# PCB1.net
KiCad netlist of a schematic drawn in EAGLE
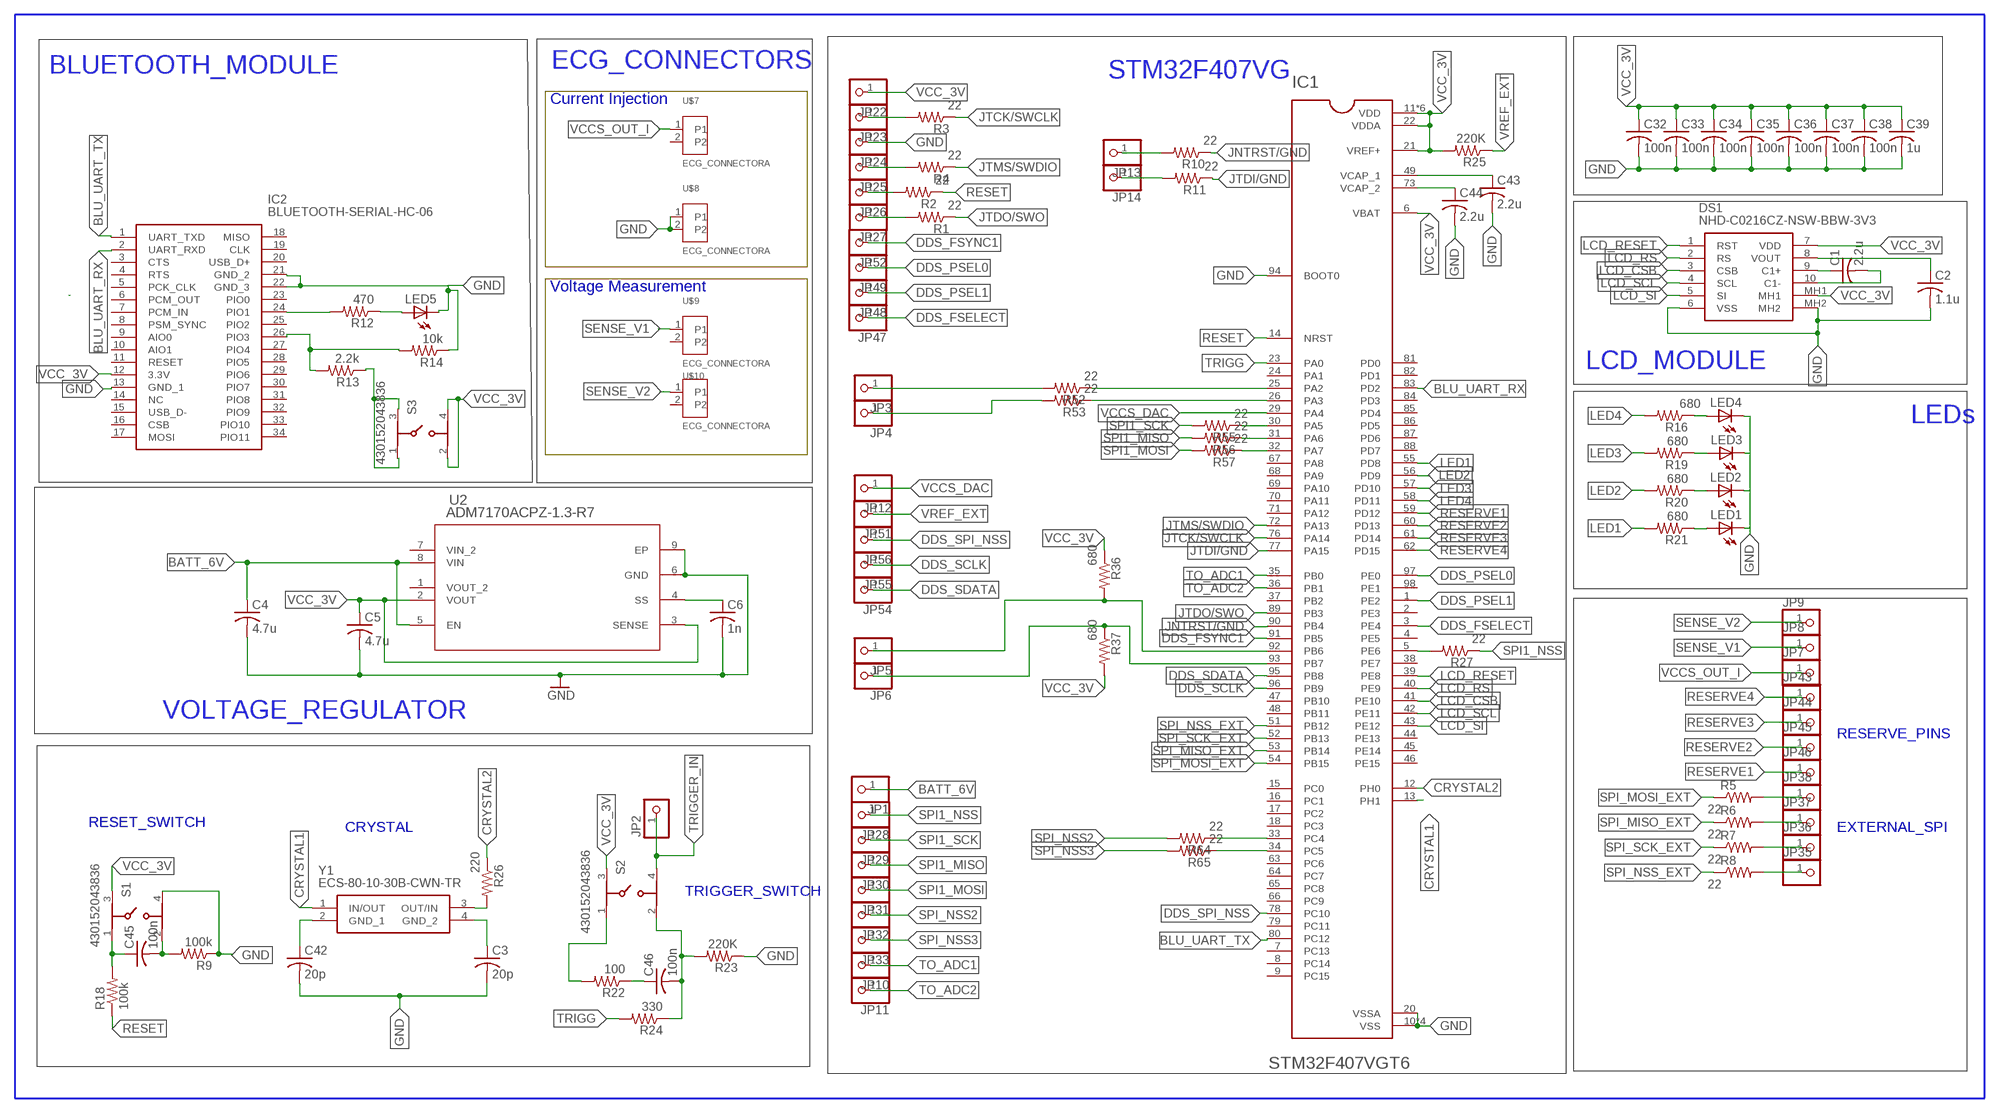
[diagram p0: schematic, sheet 1]

(export (version "E")
  (design (tool "Eeschema 10.0.6"))
  (components
    (comp (ref "C1")
      (value "2.2u")
      (footprint "eagle-import:C0603")
      (libsource (lib "eagle-import") (part "C-USC0603"))
    )
    (comp (ref "C2")
      (value "1.1u")
      (footprint "eagle-import:C0603")
      (libsource (lib "eagle-import") (part "C-USC0603"))
    )
    (comp (ref "C3")
      (value "20p")
      (footprint "eagle-import:C0603")
      (libsource (lib "eagle-import") (part "C-USC0603"))
    )
    (comp (ref "C4")
      (value "4.7u")
      (footprint "eagle-import:C0603")
      (libsource (lib "eagle-import") (part "C-USC0603"))
    )
    (comp (ref "C5")
      (value "4.7u")
      (footprint "eagle-import:C0603")
      (libsource (lib "eagle-import") (part "C-USC0603"))
    )
    (comp (ref "C6")
      (value "1n")
      (footprint "eagle-import:C0603")
      (libsource (lib "eagle-import") (part "C-USC0603"))
    )
    (comp (ref "C32")
      (value "100n")
      (footprint "eagle-import:C0603")
      (fields (field (name "SPICEPREFIX") "C"))
      (libsource (lib "eagle-import") (part "C-USC0603"))
    )
    (comp (ref "C33")
      (value "100n")
      (footprint "eagle-import:C0603")
      (fields (field (name "SPICEPREFIX") "C"))
      (libsource (lib "eagle-import") (part "C-USC0603"))
    )
    (comp (ref "C34")
      (value "100n")
      (footprint "eagle-import:C0603")
      (fields (field (name "SPICEPREFIX") "C"))
      (libsource (lib "eagle-import") (part "C-USC0603"))
    )
    (comp (ref "C35")
      (value "100n")
      (footprint "eagle-import:C0603")
      (fields (field (name "SPICEPREFIX") "C"))
      (libsource (lib "eagle-import") (part "C-USC0603"))
    )
    (comp (ref "C36")
      (value "100n")
      (footprint "eagle-import:C0603")
      (fields (field (name "SPICEPREFIX") "C"))
      (libsource (lib "eagle-import") (part "C-USC0603"))
    )
    (comp (ref "C37")
      (value "100n")
      (footprint "eagle-import:C0603")
      (fields (field (name "SPICEPREFIX") "C"))
      (libsource (lib "eagle-import") (part "C-USC0603"))
    )
    (comp (ref "C38")
      (value "100n")
      (footprint "eagle-import:C0603")
      (fields (field (name "SPICEPREFIX") "C"))
      (libsource (lib "eagle-import") (part "C-USC0603"))
    )
    (comp (ref "C39")
      (value "1u")
      (footprint "eagle-import:C0603")
      (fields (field (name "SPICEPREFIX") "C"))
      (libsource (lib "eagle-import") (part "C-USC0603"))
    )
    (comp (ref "C42")
      (value "20p")
      (footprint "eagle-import:C0603")
      (libsource (lib "eagle-import") (part "C-USC0603"))
    )
    (comp (ref "C43")
      (value "2.2u")
      (footprint "eagle-import:C0603")
      (libsource (lib "eagle-import") (part "C-USC0603"))
    )
    (comp (ref "C44")
      (value "2.2u")
      (footprint "eagle-import:C0603")
      (libsource (lib "eagle-import") (part "C-USC0603"))
    )
    (comp (ref "C45")
      (value "100n")
      (footprint "eagle-import:C0603")
      (libsource (lib "eagle-import") (part "C-USC0603"))
    )
    (comp (ref "C46")
      (value "100n")
      (footprint "eagle-import:C0603")
      (libsource (lib "eagle-import") (part "C-USC0603"))
    )
    (comp (ref "DS1")
      (value "NHD-C0216CZ-NSW-BBW-3V3")
      (footprint "eagle-import:NHDC0216CZNSWBBW3V3")
      (fields (field (name "MOUSER_PART_NUMBER") "763-C0216CZ-NSWBBW3V"))
      (libsource (lib "eagle-import") (part "NHD-C0216CZ-NSW-BBW-3V3"))
    )
    (comp (ref "IC1")
      (value "STM32F407VGT6")
      (footprint "eagle-import:QFP50P1600X1600X160-100N")
      (fields (field (name "MF") "STMicroelectronics"))
      (libsource (lib "eagle-import") (part "STM32F407VGT6"))
    )
    (comp (ref "IC2")
      (value "BLUETOOTH-SERIAL-HC-06")
      (footprint "eagle-import:BLUETOOTHSERIALHC06")
      (fields (field (name "MOUSER_PART_NUMBER") "909-BLE-SERIAL-HC-06"))
      (libsource (lib "eagle-import") (part "BLUETOOTH-SERIAL-HC-06"))
    )
    (comp (ref "JP1")
      (value "PINHD-1X1")
      (footprint "eagle-import:1X01")
      (libsource (lib "eagle-import") (part "PINHD-1X1"))
    )
    (comp (ref "JP2")
      (value "PINHD-1X1")
      (footprint "eagle-import:1X01")
      (libsource (lib "eagle-import") (part "PINHD-1X1"))
    )
    (comp (ref "JP3")
      (value "PINHD-1X1")
      (footprint "eagle-import:1X01")
      (libsource (lib "eagle-import") (part "PINHD-1X1"))
    )
    (comp (ref "JP4")
      (value "PINHD-1X1")
      (footprint "eagle-import:1X01")
      (libsource (lib "eagle-import") (part "PINHD-1X1"))
    )
    (comp (ref "JP5")
      (value "PINHD-1X1")
      (footprint "eagle-import:1X01")
      (libsource (lib "eagle-import") (part "PINHD-1X1"))
    )
    (comp (ref "JP6")
      (value "PINHD-1X1")
      (footprint "eagle-import:1X01")
      (libsource (lib "eagle-import") (part "PINHD-1X1"))
    )
    (comp (ref "JP7")
      (value "PINHD-1X1")
      (footprint "eagle-import:1X01")
      (libsource (lib "eagle-import") (part "PINHD-1X1"))
    )
    (comp (ref "JP8")
      (value "PINHD-1X1")
      (footprint "eagle-import:1X01")
      (libsource (lib "eagle-import") (part "PINHD-1X1"))
    )
    (comp (ref "JP9")
      (value "PINHD-1X1")
      (footprint "eagle-import:1X01")
      (libsource (lib "eagle-import") (part "PINHD-1X1"))
    )
    (comp (ref "JP10")
      (value "PINHD-1X1")
      (footprint "eagle-import:1X01")
      (libsource (lib "eagle-import") (part "PINHD-1X1"))
    )
    (comp (ref "JP11")
      (value "PINHD-1X1")
      (footprint "eagle-import:1X01")
      (libsource (lib "eagle-import") (part "PINHD-1X1"))
    )
    (comp (ref "JP12")
      (value "PINHD-1X1")
      (footprint "eagle-import:1X01")
      (libsource (lib "eagle-import") (part "PINHD-1X1"))
    )
    (comp (ref "JP13")
      (value "PINHD-1X1")
      (footprint "eagle-import:1X01")
      (libsource (lib "eagle-import") (part "PINHD-1X1"))
    )
    (comp (ref "JP14")
      (value "PINHD-1X1")
      (footprint "eagle-import:1X01")
      (libsource (lib "eagle-import") (part "PINHD-1X1"))
    )
    (comp (ref "JP22")
      (value "PINHD-1X1")
      (footprint "eagle-import:1X01")
      (libsource (lib "eagle-import") (part "PINHD-1X1"))
    )
    (comp (ref "JP23")
      (value "PINHD-1X1")
      (footprint "eagle-import:1X01")
      (libsource (lib "eagle-import") (part "PINHD-1X1"))
    )
    (comp (ref "JP24")
      (value "PINHD-1X1")
      (footprint "eagle-import:1X01")
      (libsource (lib "eagle-import") (part "PINHD-1X1"))
    )
    (comp (ref "JP25")
      (value "PINHD-1X1")
      (footprint "eagle-import:1X01")
      (libsource (lib "eagle-import") (part "PINHD-1X1"))
    )
    (comp (ref "JP26")
      (value "PINHD-1X1")
      (footprint "eagle-import:1X01")
      (libsource (lib "eagle-import") (part "PINHD-1X1"))
    )
    (comp (ref "JP27")
      (value "PINHD-1X1")
      (footprint "eagle-import:1X01")
      (libsource (lib "eagle-import") (part "PINHD-1X1"))
    )
    (comp (ref "JP28")
      (value "PINHD-1X1")
      (footprint "eagle-import:1X01")
      (libsource (lib "eagle-import") (part "PINHD-1X1"))
    )
    (comp (ref "JP29")
      (value "PINHD-1X1")
      (footprint "eagle-import:1X01")
      (libsource (lib "eagle-import") (part "PINHD-1X1"))
    )
    (comp (ref "JP30")
      (value "PINHD-1X1")
      (footprint "eagle-import:1X01")
      (libsource (lib "eagle-import") (part "PINHD-1X1"))
    )
    (comp (ref "JP31")
      (value "PINHD-1X1")
      (footprint "eagle-import:1X01")
      (libsource (lib "eagle-import") (part "PINHD-1X1"))
    )
    (comp (ref "JP32")
      (value "PINHD-1X1")
      (footprint "eagle-import:1X01")
      (libsource (lib "eagle-import") (part "PINHD-1X1"))
    )
    (comp (ref "JP33")
      (value "PINHD-1X1")
      (footprint "eagle-import:1X01")
      (libsource (lib "eagle-import") (part "PINHD-1X1"))
    )
    (comp (ref "JP35")
      (value "PINHD-1X1")
      (footprint "eagle-import:1X01")
      (fields (field (name "SPICEPREFIX") "X"))
      (libsource (lib "eagle-import") (part "PINHD-1X1"))
    )
    (comp (ref "JP36")
      (value "PINHD-1X1")
      (footprint "eagle-import:1X01")
      (fields (field (name "SPICEPREFIX") "X"))
      (libsource (lib "eagle-import") (part "PINHD-1X1"))
    )
    (comp (ref "JP37")
      (value "PINHD-1X1")
      (footprint "eagle-import:1X01")
      (fields (field (name "SPICEPREFIX") "X"))
      (libsource (lib "eagle-import") (part "PINHD-1X1"))
    )
    (comp (ref "JP38")
      (value "PINHD-1X1")
      (footprint "eagle-import:1X01")
      (fields (field (name "SPICEPREFIX") "X"))
      (libsource (lib "eagle-import") (part "PINHD-1X1"))
    )
    (comp (ref "JP43")
      (value "PINHD-1X1")
      (footprint "eagle-import:1X01")
      (fields (field (name "SPICEPREFIX") "X"))
      (libsource (lib "eagle-import") (part "PINHD-1X1"))
    )
    (comp (ref "JP44")
      (value "PINHD-1X1")
      (footprint "eagle-import:1X01")
      (fields (field (name "SPICEPREFIX") "X"))
      (libsource (lib "eagle-import") (part "PINHD-1X1"))
    )
    (comp (ref "JP45")
      (value "PINHD-1X1")
      (footprint "eagle-import:1X01")
      (fields (field (name "SPICEPREFIX") "X"))
      (libsource (lib "eagle-import") (part "PINHD-1X1"))
    )
    (comp (ref "JP46")
      (value "PINHD-1X1")
      (footprint "eagle-import:1X01")
      (fields (field (name "SPICEPREFIX") "X"))
      (libsource (lib "eagle-import") (part "PINHD-1X1"))
    )
    (comp (ref "JP47")
      (value "PINHD-1X1")
      (footprint "eagle-import:1X01")
      (libsource (lib "eagle-import") (part "PINHD-1X1"))
    )
    (comp (ref "JP48")
      (value "PINHD-1X1")
      (footprint "eagle-import:1X01")
      (libsource (lib "eagle-import") (part "PINHD-1X1"))
    )
    (comp (ref "JP49")
      (value "PINHD-1X1")
      (footprint "eagle-import:1X01")
      (libsource (lib "eagle-import") (part "PINHD-1X1"))
    )
    (comp (ref "JP51")
      (value "PINHD-1X1")
      (footprint "eagle-import:1X01")
      (libsource (lib "eagle-import") (part "PINHD-1X1"))
    )
    (comp (ref "JP52")
      (value "PINHD-1X1")
      (footprint "eagle-import:1X01")
      (libsource (lib "eagle-import") (part "PINHD-1X1"))
    )
    (comp (ref "JP54")
      (value "PINHD-1X1")
      (footprint "eagle-import:1X01")
      (libsource (lib "eagle-import") (part "PINHD-1X1"))
    )
    (comp (ref "JP55")
      (value "PINHD-1X1")
      (footprint "eagle-import:1X01")
      (libsource (lib "eagle-import") (part "PINHD-1X1"))
    )
    (comp (ref "JP56")
      (value "PINHD-1X1")
      (footprint "eagle-import:1X01")
      (libsource (lib "eagle-import") (part "PINHD-1X1"))
    )
    (comp (ref "LED1")
      (value "LEDCHIPLED_1206")
      (footprint "eagle-import:CHIPLED_1206")
      (libsource (lib "eagle-import") (part "LEDCHIPLED_1206"))
    )
    (comp (ref "LED2")
      (value "LEDCHIPLED_1206")
      (footprint "eagle-import:CHIPLED_1206")
      (libsource (lib "eagle-import") (part "LEDCHIPLED_1206"))
    )
    (comp (ref "LED3")
      (value "LEDCHIPLED_1206")
      (footprint "eagle-import:CHIPLED_1206")
      (libsource (lib "eagle-import") (part "LEDCHIPLED_1206"))
    )
    (comp (ref "LED4")
      (value "LEDCHIPLED_1206")
      (footprint "eagle-import:CHIPLED_1206")
      (libsource (lib "eagle-import") (part "LEDCHIPLED_1206"))
    )
    (comp (ref "LED5")
      (value "LEDCHIPLED_1206")
      (footprint "eagle-import:CHIPLED_1206")
      (libsource (lib "eagle-import") (part "LEDCHIPLED_1206"))
    )
    (comp (ref "R1")
      (value "22")
      (footprint "eagle-import:R0603")
      (libsource (lib "eagle-import") (part "R-US_R0603"))
    )
    (comp (ref "R2")
      (value "22")
      (footprint "eagle-import:R0603")
      (libsource (lib "eagle-import") (part "R-US_R0603"))
    )
    (comp (ref "R3")
      (value "22")
      (footprint "eagle-import:R0603")
      (libsource (lib "eagle-import") (part "R-US_R0603"))
    )
    (comp (ref "R4")
      (value "22")
      (footprint "eagle-import:R0603")
      (libsource (lib "eagle-import") (part "R-US_R0603"))
    )
    (comp (ref "R5")
      (value "22")
      (footprint "eagle-import:R0603")
      (fields (field (name "SPICEPREFIX") "R"))
      (libsource (lib "eagle-import") (part "R-US_R0603"))
    )
    (comp (ref "R6")
      (value "22")
      (footprint "eagle-import:R0603")
      (fields (field (name "SPICEPREFIX") "R"))
      (libsource (lib "eagle-import") (part "R-US_R0603"))
    )
    (comp (ref "R7")
      (value "22")
      (footprint "eagle-import:R0603")
      (fields (field (name "SPICEPREFIX") "R"))
      (libsource (lib "eagle-import") (part "R-US_R0603"))
    )
    (comp (ref "R8")
      (value "22")
      (footprint "eagle-import:R0603")
      (fields (field (name "SPICEPREFIX") "R"))
      (libsource (lib "eagle-import") (part "R-US_R0603"))
    )
    (comp (ref "R9")
      (value "100k")
      (footprint "eagle-import:R0603")
      (libsource (lib "eagle-import") (part "R-US_R0603"))
    )
    (comp (ref "R10")
      (value "22")
      (footprint "eagle-import:R0603")
      (libsource (lib "eagle-import") (part "R-US_R0603"))
    )
    (comp (ref "R11")
      (value "22")
      (footprint "eagle-import:R0603")
      (libsource (lib "eagle-import") (part "R-US_R0603"))
    )
    (comp (ref "R12")
      (value "470")
      (footprint "eagle-import:R0603")
      (libsource (lib "eagle-import") (part "R-US_R0603"))
    )
    (comp (ref "R13")
      (value "2.2k")
      (footprint "eagle-import:R0603")
      (libsource (lib "eagle-import") (part "R-US_R0603"))
    )
    (comp (ref "R14")
      (value "10k")
      (footprint "eagle-import:R0603")
      (libsource (lib "eagle-import") (part "R-US_R0603"))
    )
    (comp (ref "R16")
      (value "680")
      (footprint "eagle-import:R0603")
      (libsource (lib "eagle-import") (part "R-US_R0603"))
    )
    (comp (ref "R18")
      (value "100k")
      (footprint "eagle-import:R0603")
      (libsource (lib "eagle-import") (part "R-US_R0603"))
    )
    (comp (ref "R19")
      (value "680")
      (footprint "eagle-import:R0603")
      (libsource (lib "eagle-import") (part "R-US_R0603"))
    )
    (comp (ref "R20")
      (value "680")
      (footprint "eagle-import:R0603")
      (libsource (lib "eagle-import") (part "R-US_R0603"))
    )
    (comp (ref "R21")
      (value "680")
      (footprint "eagle-import:R0603")
      (libsource (lib "eagle-import") (part "R-US_R0603"))
    )
    (comp (ref "R22")
      (value "100")
      (footprint "eagle-import:R0603")
      (libsource (lib "eagle-import") (part "R-US_R0603"))
    )
    (comp (ref "R23")
      (value "220K")
      (footprint "eagle-import:R0603")
      (libsource (lib "eagle-import") (part "R-US_R0603"))
    )
    (comp (ref "R24")
      (value "330")
      (footprint "eagle-import:R0603")
      (libsource (lib "eagle-import") (part "R-US_R0603"))
    )
    (comp (ref "R25")
      (value "220K")
      (footprint "eagle-import:R0603")
      (libsource (lib "eagle-import") (part "R-US_R0603"))
    )
    (comp (ref "R26")
      (value "220")
      (footprint "eagle-import:R0603")
      (libsource (lib "eagle-import") (part "R-US_R0603"))
    )
    (comp (ref "R27")
      (value "22")
      (footprint "eagle-import:R0603")
      (libsource (lib "eagle-import") (part "R-US_R0603"))
    )
    (comp (ref "R36")
      (value "680")
      (footprint "eagle-import:R0603")
      (libsource (lib "eagle-import") (part "R-US_R0603"))
    )
    (comp (ref "R37")
      (value "680")
      (footprint "eagle-import:R0603")
      (libsource (lib "eagle-import") (part "R-US_R0603"))
    )
    (comp (ref "R52")
      (value "22")
      (footprint "eagle-import:R0603")
      (libsource (lib "eagle-import") (part "R-US_R0603"))
    )
    (comp (ref "R53")
      (value "22")
      (footprint "eagle-import:R0603")
      (libsource (lib "eagle-import") (part "R-US_R0603"))
    )
    (comp (ref "R55")
      (value "22")
      (footprint "eagle-import:R0603")
      (libsource (lib "eagle-import") (part "R-US_R0603"))
    )
    (comp (ref "R56")
      (value "22")
      (footprint "eagle-import:R0603")
      (libsource (lib "eagle-import") (part "R-US_R0603"))
    )
    (comp (ref "R57")
      (value "22")
      (footprint "eagle-import:R0603")
      (libsource (lib "eagle-import") (part "R-US_R0603"))
    )
    (comp (ref "R64")
      (value "22")
      (footprint "eagle-import:R0603")
      (libsource (lib "eagle-import") (part "R-US_R0603"))
    )
    (comp (ref "R65")
      (value "22")
      (footprint "eagle-import:R0603")
      (libsource (lib "eagle-import") (part "R-US_R0603"))
    )
    (comp (ref "S1")
      (value "430152043836")
      (footprint "eagle-import:430152043836")
      (fields (field (name "MF") "Wurth Electronics Inc."))
      (libsource (lib "eagle-import") (part "430152043836"))
    )
    (comp (ref "S2")
      (value "430152043836")
      (footprint "eagle-import:430152043836")
      (fields (field (name "MF") "Wurth Electronics Inc."))
      (libsource (lib "eagle-import") (part "430152043836"))
    )
    (comp (ref "S3")
      (value "430152043836")
      (footprint "eagle-import:430152043836")
      (fields (field (name "MF") "Wurth Electronics Inc."))
      (libsource (lib "eagle-import") (part "430152043836"))
    )
    (comp (ref "U$7")
      (value "ECG_CONNECTORA")
      (footprint "eagle-import:ECG_CONNECTOR")
      (libsource (lib "eagle-import") (part "ECG_CONNECTORA"))
    )
    (comp (ref "U$8")
      (value "ECG_CONNECTORA")
      (footprint "eagle-import:ECG_CONNECTOR")
      (libsource (lib "eagle-import") (part "ECG_CONNECTORA"))
    )
    (comp (ref "U$9")
      (value "ECG_CONNECTORA")
      (footprint "eagle-import:ECG_CONNECTOR")
      (libsource (lib "eagle-import") (part "ECG_CONNECTORA"))
    )
    (comp (ref "U$10")
      (value "ECG_CONNECTORA")
      (footprint "eagle-import:ECG_CONNECTOR")
      (libsource (lib "eagle-import") (part "ECG_CONNECTORA"))
    )
    (comp (ref "U2")
      (value "ADM7170ACPZ-1.3-R7")
      (footprint "eagle-import:CP_8_21")
      (fields (field (name "MANUFACTURER_PART_NUMBER") "ADM7170ACPZ1.3R7"))
      (libsource (lib "eagle-import") (part "ADM7170ACPZ-1.3-R7"))
    )
    (comp (ref "Y1")
      (value "ECS-80-10-30B-CWN-TR")
      (footprint "eagle-import:ECS801830BAGNTR")
      (fields (field (name "MOUSER_PART_NUMBER") "520-80-10-30B-CWNT"))
      (libsource (lib "eagle-import") (part "ECS-80-10-30B-CWN-TR"))
    )
  )
  (nets
    (net (code "1") (name "BATT_6V") (class "Default")
      (node (ref "C4") (pin "1") (pinfunction "1_1") (pintype "passive"))
      (node (ref "JP1") (pin "1") (pinfunction "1_1") (pintype "passive"))
      (node (ref "U2") (pin "5") (pinfunction "EN_5") (pintype "passive"))
      (node (ref "U2") (pin "8") (pinfunction "VIN_8") (pintype "passive"))
    )
    (net (code "2") (name "BLU_UART_RX") (class "Default")
      (node (ref "IC1") (pin "83") (pinfunction "PD2_83") (pintype "bidirectional"))
      (node (ref "IC2") (pin "2") (pinfunction "UART_RXD_2") (pintype "bidirectional"))
    )
    (net (code "3") (name "BLU_UART_TX") (class "Default")
      (node (ref "IC1") (pin "80") (pinfunction "PC12_80") (pintype "bidirectional"))
      (node (ref "IC2") (pin "1") (pinfunction "UART_TXD_1") (pintype "bidirectional"))
    )
    (net (code "4") (name "CRYSTAL1") (class "Default")
      (node (ref "IC1") (pin "13") (pinfunction "PH1_13") (pintype "bidirectional"))
      (node (ref "Y1") (pin "1") (pinfunction "IN/OUT_1") (pintype "bidirectional"))
    )
    (net (code "5") (name "CRYSTAL2") (class "Default")
      (node (ref "IC1") (pin "12") (pinfunction "PH0_12") (pintype "bidirectional"))
      (node (ref "R26") (pin "1") (pinfunction "1_1") (pintype "passive"))
    )
    (net (code "6") (name "DDS_FSELECT") (class "Default")
      (node (ref "IC1") (pin "3") (pinfunction "PE4_3") (pintype "bidirectional"))
      (node (ref "JP47") (pin "1") (pinfunction "1_1") (pintype "passive"))
    )
    (net (code "7") (name "DDS_FSYNC1") (class "Default")
      (node (ref "IC1") (pin "91") (pinfunction "PB5_91") (pintype "bidirectional"))
      (node (ref "JP52") (pin "1") (pinfunction "1_1") (pintype "passive"))
    )
    (net (code "8") (name "DDS_PSEL0") (class "Default")
      (node (ref "IC1") (pin "97") (pinfunction "PE0_97") (pintype "bidirectional"))
      (node (ref "JP49") (pin "1") (pinfunction "1_1") (pintype "passive"))
    )
    (net (code "9") (name "DDS_PSEL1") (class "Default")
      (node (ref "IC1") (pin "1") (pinfunction "PE2_1") (pintype "bidirectional"))
      (node (ref "JP48") (pin "1") (pinfunction "1_1") (pintype "passive"))
    )
    (net (code "10") (name "DDS_SCLK") (class "Default")
      (node (ref "IC1") (pin "96") (pinfunction "PB9_96") (pintype "bidirectional"))
      (node (ref "JP55") (pin "1") (pinfunction "1_1") (pintype "passive"))
    )
    (net (code "11") (name "DDS_SDATA") (class "Default")
      (node (ref "IC1") (pin "95") (pinfunction "PB8_95") (pintype "bidirectional"))
      (node (ref "JP54") (pin "1") (pinfunction "1_1") (pintype "passive"))
    )
    (net (code "12") (name "DDS_SPI_NSS") (class "Default")
      (node (ref "IC1") (pin "78") (pinfunction "PC10_78") (pintype "bidirectional"))
      (node (ref "JP56") (pin "1") (pinfunction "1_1") (pintype "passive"))
    )
    (net (code "13") (name "GND") (class "Default")
      (node (ref "C2") (pin "2") (pinfunction "2_2") (pintype "passive"))
      (node (ref "C3") (pin "2") (pinfunction "2_2") (pintype "passive"))
      (node (ref "C32") (pin "2") (pinfunction "2_2") (pintype "passive"))
      (node (ref "C33") (pin "2") (pinfunction "2_2") (pintype "passive"))
      (node (ref "C34") (pin "2") (pinfunction "2_2") (pintype "passive"))
      (node (ref "C35") (pin "2") (pinfunction "2_2") (pintype "passive"))
      (node (ref "C36") (pin "2") (pinfunction "2_2") (pintype "passive"))
      (node (ref "C37") (pin "2") (pinfunction "2_2") (pintype "passive"))
      (node (ref "C38") (pin "2") (pinfunction "2_2") (pintype "passive"))
      (node (ref "C39") (pin "2") (pinfunction "2_2") (pintype "passive"))
      (node (ref "C4") (pin "2") (pinfunction "2_2") (pintype "passive"))
      (node (ref "C42") (pin "1") (pinfunction "1_1") (pintype "passive"))
      (node (ref "C42") (pin "2") (pinfunction "2_2") (pintype "passive"))
      (node (ref "C43") (pin "2") (pinfunction "2_2") (pintype "passive"))
      (node (ref "C44") (pin "2") (pinfunction "2_2") (pintype "passive"))
      (node (ref "C5") (pin "2") (pinfunction "2_2") (pintype "passive"))
      (node (ref "C6") (pin "2") (pinfunction "2_2") (pintype "passive"))
      (node (ref "DS1") (pin "6") (pinfunction "VSS_6") (pintype "bidirectional"))
      (node (ref "DS1") (pin "MH2") (pinfunction "MH2_MH2") (pintype "bidirectional"))
      (node (ref "IC1") (pin "10") (pinfunction "VSS_10") (pintype "passive"))
      (node (ref "IC1") (pin "20") (pinfunction "VSSA_20") (pintype "passive"))
      (node (ref "IC1") (pin "27") (pinfunction "VSS_27") (pintype "passive"))
      (node (ref "IC1") (pin "74") (pinfunction "VSS_74") (pintype "passive"))
      (node (ref "IC1") (pin "94") (pinfunction "BOOT0_94") (pintype "input"))
      (node (ref "IC1") (pin "99") (pinfunction "VSS_99") (pintype "passive"))
      (node (ref "IC2") (pin "13") (pinfunction "GND_1_13") (pintype "bidirectional"))
      (node (ref "IC2") (pin "21") (pinfunction "GND_2_21") (pintype "bidirectional"))
      (node (ref "IC2") (pin "22") (pinfunction "GND_3_22") (pintype "bidirectional"))
      (node (ref "JP24") (pin "1") (pinfunction "1_1") (pintype "passive"))
      (node (ref "LED1") (pin "C") (pinfunction "C_C") (pintype "passive"))
      (node (ref "LED2") (pin "C") (pinfunction "C_C") (pintype "passive"))
      (node (ref "LED3") (pin "C") (pinfunction "C_C") (pintype "passive"))
      (node (ref "LED4") (pin "C") (pinfunction "C_C") (pintype "passive"))
      (node (ref "LED5") (pin "C") (pinfunction "C_C") (pintype "passive"))
      (node (ref "R14") (pin "1") (pinfunction "1_1") (pintype "passive"))
      (node (ref "R23") (pin "1") (pinfunction "1_1") (pintype "passive"))
      (node (ref "R9") (pin "1") (pinfunction "1_1") (pintype "passive"))
      (node (ref "S1") (pin "4") (pinfunction "4_4") (pintype "passive"))
      (node (ref "U$8") (pin "1") (pinfunction "P1_1") (pintype "bidirectional"))
      (node (ref "U$8") (pin "2") (pinfunction "P2_2") (pintype "bidirectional"))
      (node (ref "U2") (pin "6") (pinfunction "GND_6") (pintype "passive"))
      (node (ref "U2") (pin "9") (pinfunction "EP_9") (pintype "passive"))
      (node (ref "Y1") (pin "2") (pinfunction "GND_1_2") (pintype "bidirectional"))
    )
    (net (code "14") (name "JNTRST{slash}GND") (class "Default")
      (node (ref "IC1") (pin "90") (pinfunction "PB4_90") (pintype "bidirectional"))
      (node (ref "R10") (pin "1") (pinfunction "1_1") (pintype "passive"))
    )
    (net (code "15") (name "JTCK{slash}SWCLK") (class "Default")
      (node (ref "IC1") (pin "76") (pinfunction "PA14_76") (pintype "bidirectional"))
      (node (ref "R3") (pin "1") (pinfunction "1_1") (pintype "passive"))
    )
    (net (code "16") (name "JTDI{slash}GND") (class "Default")
      (node (ref "IC1") (pin "77") (pinfunction "PA15_77") (pintype "bidirectional"))
      (node (ref "R11") (pin "1") (pinfunction "1_1") (pintype "passive"))
    )
    (net (code "17") (name "JTDO{slash}SWO") (class "Default")
      (node (ref "IC1") (pin "89") (pinfunction "PB3_89") (pintype "bidirectional"))
      (node (ref "R1") (pin "1") (pinfunction "1_1") (pintype "passive"))
    )
    (net (code "18") (name "JTMS{slash}SWDIO") (class "Default")
      (node (ref "IC1") (pin "72") (pinfunction "PA13_72") (pintype "bidirectional"))
      (node (ref "R4") (pin "1") (pinfunction "1_1") (pintype "passive"))
    )
    (net (code "19") (name "LCD_CSB") (class "Default")
      (node (ref "DS1") (pin "3") (pinfunction "CSB_3") (pintype "bidirectional"))
      (node (ref "IC1") (pin "41") (pinfunction "PE10_41") (pintype "bidirectional"))
    )
    (net (code "20") (name "LCD_RESET") (class "Default")
      (node (ref "DS1") (pin "1") (pinfunction "RST_1") (pintype "bidirectional"))
      (node (ref "IC1") (pin "39") (pinfunction "PE8_39") (pintype "bidirectional"))
    )
    (net (code "21") (name "LCD_RS") (class "Default")
      (node (ref "DS1") (pin "2") (pinfunction "RS_2") (pintype "bidirectional"))
      (node (ref "IC1") (pin "40") (pinfunction "PE9_40") (pintype "bidirectional"))
    )
    (net (code "22") (name "LCD_SCL") (class "Default")
      (node (ref "DS1") (pin "4") (pinfunction "SCL_4") (pintype "bidirectional"))
      (node (ref "IC1") (pin "42") (pinfunction "PE11_42") (pintype "bidirectional"))
    )
    (net (code "23") (name "LCD_SI") (class "Default")
      (node (ref "DS1") (pin "5") (pinfunction "SI_5") (pintype "bidirectional"))
      (node (ref "IC1") (pin "43") (pinfunction "PE12_43") (pintype "bidirectional"))
    )
    (net (code "24") (name "LED1") (class "Default")
      (node (ref "IC1") (pin "55") (pinfunction "PD8_55") (pintype "bidirectional"))
      (node (ref "R21") (pin "2") (pinfunction "2_2") (pintype "passive"))
    )
    (net (code "25") (name "LED2") (class "Default")
      (node (ref "IC1") (pin "56") (pinfunction "PD9_56") (pintype "bidirectional"))
      (node (ref "R20") (pin "2") (pinfunction "2_2") (pintype "passive"))
    )
    (net (code "26") (name "LED3") (class "Default")
      (node (ref "IC1") (pin "57") (pinfunction "PD10_57") (pintype "bidirectional"))
      (node (ref "R19") (pin "2") (pinfunction "2_2") (pintype "passive"))
    )
    (net (code "27") (name "LED4") (class "Default")
      (node (ref "IC1") (pin "58") (pinfunction "PD11_58") (pintype "bidirectional"))
      (node (ref "R16") (pin "2") (pinfunction "2_2") (pintype "passive"))
    )
    (net (code "28") (name "Net-(C45-Pad1)") (class "Default")
      (node (ref "C45") (pin "1") (pinfunction "1_1") (pintype "passive"))
      (node (ref "R18") (pin "2") (pinfunction "2_2") (pintype "passive"))
      (node (ref "S1") (pin "1") (pinfunction "1_1") (pintype "passive"))
    )
    (net (code "29") (name "Net-(C45-Pad2)") (class "Default")
      (node (ref "C45") (pin "2") (pinfunction "2_2") (pintype "passive"))
      (node (ref "R9") (pin "2") (pinfunction "2_2") (pintype "passive"))
      (node (ref "S1") (pin "2") (pinfunction "2_2") (pintype "passive"))
    )
    (net (code "30") (name "Net-(C46-Pad1)") (class "Default")
      (node (ref "C46") (pin "1") (pinfunction "1_1") (pintype "passive"))
      (node (ref "R22") (pin "1") (pinfunction "1_1") (pintype "passive"))
    )
    (net (code "31") (name "Net-(C46-Pad2)") (class "Default")
      (node (ref "C46") (pin "2") (pinfunction "2_2") (pintype "passive"))
      (node (ref "R23") (pin "2") (pinfunction "2_2") (pintype "passive"))
      (node (ref "R24") (pin "1") (pinfunction "1_1") (pintype "passive"))
      (node (ref "S2") (pin "2") (pinfunction "2_2") (pintype "passive"))
    )
    (net (code "32") (name "Net-(DS1-C1+)") (class "Default")
      (node (ref "C1") (pin "1") (pinfunction "1_1") (pintype "passive"))
      (node (ref "DS1") (pin "9") (pinfunction "C1+_9") (pintype "bidirectional"))
    )
    (net (code "33") (name "Net-(DS1-C1-)") (class "Default")
      (node (ref "C1") (pin "2") (pinfunction "2_2") (pintype "passive"))
      (node (ref "DS1") (pin "10") (pinfunction "C1-_10") (pintype "bidirectional"))
    )
    (net (code "34") (name "Net-(DS1-VOUT)") (class "Default")
      (node (ref "C2") (pin "1") (pinfunction "1_1") (pintype "passive"))
      (node (ref "DS1") (pin "8") (pinfunction "VOUT_8") (pintype "bidirectional"))
    )
    (net (code "35") (name "Net-(IC1-PA2)") (class "Default")
      (node (ref "IC1") (pin "25") (pinfunction "PA2_25") (pintype "bidirectional"))
      (node (ref "R52") (pin "1") (pinfunction "1_1") (pintype "passive"))
    )
    (net (code "36") (name "Net-(IC1-PA3)") (class "Default")
      (node (ref "IC1") (pin "26") (pinfunction "PA3_26") (pintype "bidirectional"))
      (node (ref "R53") (pin "1") (pinfunction "1_1") (pintype "passive"))
    )
    (net (code "37") (name "Net-(IC1-PA5)") (class "Default")
      (node (ref "IC1") (pin "30") (pinfunction "PA5_30") (pintype "bidirectional"))
      (node (ref "R55") (pin "1") (pinfunction "1_1") (pintype "passive"))
    )
    (net (code "38") (name "Net-(IC1-PA6)") (class "Default")
      (node (ref "IC1") (pin "31") (pinfunction "PA6_31") (pintype "bidirectional"))
      (node (ref "R56") (pin "1") (pinfunction "1_1") (pintype "passive"))
    )
    (net (code "39") (name "Net-(IC1-PA7)") (class "Default")
      (node (ref "IC1") (pin "32") (pinfunction "PA7_32") (pintype "bidirectional"))
      (node (ref "R57") (pin "1") (pinfunction "1_1") (pintype "passive"))
    )
    (net (code "40") (name "Net-(IC1-PB6)") (class "Default")
      (node (ref "IC1") (pin "92") (pinfunction "PB6_92") (pintype "bidirectional"))
      (node (ref "JP5") (pin "1") (pinfunction "1_1") (pintype "passive"))
      (node (ref "R36") (pin "2") (pinfunction "2_2") (pintype "passive"))
    )
    (net (code "41") (name "Net-(IC1-PB7)") (class "Default")
      (node (ref "IC1") (pin "93") (pinfunction "PB7_93") (pintype "bidirectional"))
      (node (ref "JP6") (pin "1") (pinfunction "1_1") (pintype "passive"))
      (node (ref "R37") (pin "1") (pinfunction "1_1") (pintype "passive"))
    )
    (net (code "42") (name "Net-(IC1-PC4)") (class "Default")
      (node (ref "IC1") (pin "33") (pinfunction "PC4_33") (pintype "bidirectional"))
      (node (ref "R64") (pin "1") (pinfunction "1_1") (pintype "passive"))
    )
    (net (code "43") (name "Net-(IC1-PC5)") (class "Default")
      (node (ref "IC1") (pin "34") (pinfunction "PC5_34") (pintype "bidirectional"))
      (node (ref "R65") (pin "1") (pinfunction "1_1") (pintype "passive"))
    )
    (net (code "44") (name "Net-(IC1-PE6)") (class "Default")
      (node (ref "IC1") (pin "5") (pinfunction "PE6_5") (pintype "bidirectional"))
      (node (ref "R27") (pin "2") (pinfunction "2_2") (pintype "passive"))
    )
    (net (code "45") (name "Net-(IC1-VCAP_1)") (class "Default")
      (node (ref "C43") (pin "1") (pinfunction "1_1") (pintype "passive"))
      (node (ref "IC1") (pin "49") (pinfunction "VCAP_1_49") (pintype "power_in"))
    )
    (net (code "46") (name "Net-(IC1-VCAP_2)") (class "Default")
      (node (ref "C44") (pin "1") (pinfunction "1_1") (pintype "passive"))
      (node (ref "IC1") (pin "73") (pinfunction "VCAP_2_73") (pintype "power_in"))
    )
    (net (code "47") (name "Net-(IC2-PIO1)") (class "Default")
      (node (ref "IC2") (pin "24") (pinfunction "PIO1_24") (pintype "bidirectional"))
      (node (ref "R12") (pin "2") (pinfunction "2_2") (pintype "passive"))
    )
    (net (code "48") (name "Net-(IC2-PIO3)") (class "Default")
      (node (ref "IC2") (pin "26") (pinfunction "PIO3_26") (pintype "bidirectional"))
      (node (ref "R13") (pin "2") (pinfunction "2_2") (pintype "passive"))
      (node (ref "R14") (pin "2") (pinfunction "2_2") (pintype "passive"))
    )
    (net (code "49") (name "Net-(JP3-Pad1)") (class "Default")
      (node (ref "JP3") (pin "1") (pinfunction "1_1") (pintype "passive"))
      (node (ref "R52") (pin "2") (pinfunction "2_2") (pintype "passive"))
    )
    (net (code "50") (name "Net-(JP4-Pad1)") (class "Default")
      (node (ref "JP4") (pin "1") (pinfunction "1_1") (pintype "passive"))
      (node (ref "R53") (pin "2") (pinfunction "2_2") (pintype "passive"))
    )
    (net (code "51") (name "Net-(JP13-Pad1)") (class "Default")
      (node (ref "JP13") (pin "1") (pinfunction "1_1") (pintype "passive"))
      (node (ref "R10") (pin "2") (pinfunction "2_2") (pintype "passive"))
    )
    (net (code "52") (name "Net-(JP14-Pad1)") (class "Default")
      (node (ref "JP14") (pin "1") (pinfunction "1_1") (pintype "passive"))
      (node (ref "R11") (pin "2") (pinfunction "2_2") (pintype "passive"))
    )
    (net (code "53") (name "Net-(JP23-Pad1)") (class "Default")
      (node (ref "JP23") (pin "1") (pinfunction "1_1") (pintype "passive"))
      (node (ref "R3") (pin "2") (pinfunction "2_2") (pintype "passive"))
    )
    (net (code "54") (name "Net-(JP25-Pad1)") (class "Default")
      (node (ref "JP25") (pin "1") (pinfunction "1_1") (pintype "passive"))
      (node (ref "R4") (pin "2") (pinfunction "2_2") (pintype "passive"))
    )
    (net (code "55") (name "Net-(JP26-Pad1)") (class "Default")
      (node (ref "JP26") (pin "1") (pinfunction "1_1") (pintype "passive"))
      (node (ref "R2") (pin "2") (pinfunction "2_2") (pintype "passive"))
    )
    (net (code "56") (name "Net-(JP27-Pad1)") (class "Default")
      (node (ref "JP27") (pin "1") (pinfunction "1_1") (pintype "passive"))
      (node (ref "R1") (pin "2") (pinfunction "2_2") (pintype "passive"))
    )
    (net (code "57") (name "Net-(JP35-Pad1)") (class "Default")
      (node (ref "JP35") (pin "1") (pinfunction "1_1") (pintype "passive"))
      (node (ref "R8") (pin "2") (pinfunction "2_2") (pintype "passive"))
    )
    (net (code "58") (name "Net-(JP36-Pad1)") (class "Default")
      (node (ref "JP36") (pin "1") (pinfunction "1_1") (pintype "passive"))
      (node (ref "R7") (pin "2") (pinfunction "2_2") (pintype "passive"))
    )
    (net (code "59") (name "Net-(JP37-Pad1)") (class "Default")
      (node (ref "JP37") (pin "1") (pinfunction "1_1") (pintype "passive"))
      (node (ref "R6") (pin "2") (pinfunction "2_2") (pintype "passive"))
    )
    (net (code "60") (name "Net-(JP38-Pad1)") (class "Default")
      (node (ref "JP38") (pin "1") (pinfunction "1_1") (pintype "passive"))
      (node (ref "R5") (pin "2") (pinfunction "2_2") (pintype "passive"))
    )
    (net (code "61") (name "Net-(LED1-PadA)") (class "Default")
      (node (ref "LED1") (pin "A") (pinfunction "A_A") (pintype "passive"))
      (node (ref "R21") (pin "1") (pinfunction "1_1") (pintype "passive"))
    )
    (net (code "62") (name "Net-(LED2-PadA)") (class "Default")
      (node (ref "LED2") (pin "A") (pinfunction "A_A") (pintype "passive"))
      (node (ref "R20") (pin "1") (pinfunction "1_1") (pintype "passive"))
    )
    (net (code "63") (name "Net-(LED3-PadA)") (class "Default")
      (node (ref "LED3") (pin "A") (pinfunction "A_A") (pintype "passive"))
      (node (ref "R19") (pin "1") (pinfunction "1_1") (pintype "passive"))
    )
    (net (code "64") (name "Net-(LED4-PadA)") (class "Default")
      (node (ref "LED4") (pin "A") (pinfunction "A_A") (pintype "passive"))
      (node (ref "R16") (pin "1") (pinfunction "1_1") (pintype "passive"))
    )
    (net (code "65") (name "Net-(LED5-PadA)") (class "Default")
      (node (ref "LED5") (pin "A") (pinfunction "A_A") (pintype "passive"))
      (node (ref "R12") (pin "1") (pinfunction "1_1") (pintype "passive"))
    )
    (net (code "66") (name "Net-(R13-Pad1)") (class "Default")
      (node (ref "R13") (pin "1") (pinfunction "1_1") (pintype "passive"))
      (node (ref "S3") (pin "1") (pinfunction "1_1") (pintype "passive"))
      (node (ref "S3") (pin "3") (pinfunction "3_3") (pintype "passive"))
    )
    (net (code "67") (name "Net-(R22-Pad2)") (class "Default")
      (node (ref "R22") (pin "2") (pinfunction "2_2") (pintype "passive"))
      (node (ref "S2") (pin "1") (pinfunction "1_1") (pintype "passive"))
    )
    (net (code "68") (name "Net-(U2-SS)") (class "Default")
      (node (ref "C6") (pin "1") (pinfunction "1_1") (pintype "passive"))
      (node (ref "U2") (pin "4") (pinfunction "SS_4") (pintype "passive"))
    )
    (net (code "69") (name "Net-(Y1-GND_2)") (class "Default")
      (node (ref "C3") (pin "1") (pinfunction "1_1") (pintype "passive"))
      (node (ref "Y1") (pin "4") (pinfunction "GND_2_4") (pintype "bidirectional"))
    )
    (net (code "70") (name "Net-(Y1-OUT{slash}IN)") (class "Default")
      (node (ref "R26") (pin "2") (pinfunction "2_2") (pintype "passive"))
      (node (ref "Y1") (pin "3") (pinfunction "OUT/IN_3") (pintype "bidirectional"))
    )
    (net (code "71") (name "RESERVE1") (class "Default")
      (node (ref "IC1") (pin "59") (pinfunction "PD12_59") (pintype "bidirectional"))
      (node (ref "JP46") (pin "1") (pinfunction "1_1") (pintype "passive"))
    )
    (net (code "72") (name "RESERVE2") (class "Default")
      (node (ref "IC1") (pin "60") (pinfunction "PD13_60") (pintype "bidirectional"))
      (node (ref "JP45") (pin "1") (pinfunction "1_1") (pintype "passive"))
    )
    (net (code "73") (name "RESERVE3") (class "Default")
      (node (ref "IC1") (pin "61") (pinfunction "PD14_61") (pintype "bidirectional"))
      (node (ref "JP44") (pin "1") (pinfunction "1_1") (pintype "passive"))
    )
    (net (code "74") (name "RESERVE4") (class "Default")
      (node (ref "IC1") (pin "62") (pinfunction "PD15_62") (pintype "bidirectional"))
      (node (ref "JP43") (pin "1") (pinfunction "1_1") (pintype "passive"))
    )
    (net (code "75") (name "RESET") (class "Default")
      (node (ref "IC1") (pin "14") (pinfunction "NRST_14") (pintype "bidirectional"))
      (node (ref "R18") (pin "1") (pinfunction "1_1") (pintype "passive"))
      (node (ref "R2") (pin "1") (pinfunction "1_1") (pintype "passive"))
    )
    (net (code "76") (name "SENSE_V1") (class "Default")
      (node (ref "JP8") (pin "1") (pinfunction "1_1") (pintype "passive"))
      (node (ref "U$9") (pin "1") (pinfunction "P1_1") (pintype "bidirectional"))
    )
    (net (code "77") (name "SENSE_V2") (class "Default")
      (node (ref "JP9") (pin "1") (pinfunction "1_1") (pintype "passive"))
      (node (ref "U$10") (pin "1") (pinfunction "P1_1") (pintype "bidirectional"))
    )
    (net (code "78") (name "SPI1_MISO") (class "Default")
      (node (ref "JP30") (pin "1") (pinfunction "1_1") (pintype "passive"))
      (node (ref "R56") (pin "2") (pinfunction "2_2") (pintype "passive"))
    )
    (net (code "79") (name "SPI1_MOSI") (class "Default")
      (node (ref "JP31") (pin "1") (pinfunction "1_1") (pintype "passive"))
      (node (ref "R57") (pin "2") (pinfunction "2_2") (pintype "passive"))
    )
    (net (code "80") (name "SPI1_NSS") (class "Default")
      (node (ref "JP28") (pin "1") (pinfunction "1_1") (pintype "passive"))
      (node (ref "R27") (pin "1") (pinfunction "1_1") (pintype "passive"))
    )
    (net (code "81") (name "SPI1_SCK") (class "Default")
      (node (ref "JP29") (pin "1") (pinfunction "1_1") (pintype "passive"))
      (node (ref "R55") (pin "2") (pinfunction "2_2") (pintype "passive"))
    )
    (net (code "82") (name "SPI_MISO_EXT") (class "Default")
      (node (ref "IC1") (pin "53") (pinfunction "PB14_53") (pintype "bidirectional"))
      (node (ref "R6") (pin "1") (pinfunction "1_1") (pintype "passive"))
    )
    (net (code "83") (name "SPI_MOSI_EXT") (class "Default")
      (node (ref "IC1") (pin "54") (pinfunction "PB15_54") (pintype "bidirectional"))
      (node (ref "R5") (pin "1") (pinfunction "1_1") (pintype "passive"))
    )
    (net (code "84") (name "SPI_NSS2") (class "Default")
      (node (ref "JP32") (pin "1") (pinfunction "1_1") (pintype "passive"))
      (node (ref "R64") (pin "2") (pinfunction "2_2") (pintype "passive"))
    )
    (net (code "85") (name "SPI_NSS3") (class "Default")
      (node (ref "JP33") (pin "1") (pinfunction "1_1") (pintype "passive"))
      (node (ref "R65") (pin "2") (pinfunction "2_2") (pintype "passive"))
    )
    (net (code "86") (name "SPI_NSS_EXT") (class "Default")
      (node (ref "IC1") (pin "51") (pinfunction "PB12_51") (pintype "bidirectional"))
      (node (ref "R8") (pin "1") (pinfunction "1_1") (pintype "passive"))
    )
    (net (code "87") (name "SPI_SCK_EXT") (class "Default")
      (node (ref "IC1") (pin "52") (pinfunction "PB13_52") (pintype "bidirectional"))
      (node (ref "R7") (pin "1") (pinfunction "1_1") (pintype "passive"))
    )
    (net (code "88") (name "TO_ADC1") (class "Default")
      (node (ref "IC1") (pin "35") (pinfunction "PB0_35") (pintype "bidirectional"))
      (node (ref "JP10") (pin "1") (pinfunction "1_1") (pintype "passive"))
    )
    (net (code "89") (name "TO_ADC2") (class "Default")
      (node (ref "IC1") (pin "36") (pinfunction "PB1_36") (pintype "bidirectional"))
      (node (ref "JP11") (pin "1") (pinfunction "1_1") (pintype "passive"))
    )
    (net (code "90") (name "TRIGG") (class "Default")
      (node (ref "IC1") (pin "23") (pinfunction "PA0_23") (pintype "bidirectional"))
      (node (ref "R24") (pin "2") (pinfunction "2_2") (pintype "passive"))
    )
    (net (code "91") (name "TRIGGER_IN") (class "Default")
      (node (ref "JP2") (pin "1") (pinfunction "1_1") (pintype "passive"))
      (node (ref "S2") (pin "4") (pinfunction "4_4") (pintype "passive"))
    )
    (net (code "92") (name "VCCS_DAC") (class "Default")
      (node (ref "IC1") (pin "29") (pinfunction "PA4_29") (pintype "bidirectional"))
      (node (ref "JP12") (pin "1") (pinfunction "1_1") (pintype "passive"))
    )
    (net (code "93") (name "VCCS_OUT_I") (class "Default")
      (node (ref "JP7") (pin "1") (pinfunction "1_1") (pintype "passive"))
      (node (ref "U$7") (pin "1") (pinfunction "P1_1") (pintype "bidirectional"))
    )
    (net (code "94") (name "VCC_3V") (class "Default")
      (node (ref "C32") (pin "1") (pinfunction "1_1") (pintype "passive"))
      (node (ref "C33") (pin "1") (pinfunction "1_1") (pintype "passive"))
      (node (ref "C34") (pin "1") (pinfunction "1_1") (pintype "passive"))
      (node (ref "C35") (pin "1") (pinfunction "1_1") (pintype "passive"))
      (node (ref "C36") (pin "1") (pinfunction "1_1") (pintype "passive"))
      (node (ref "C37") (pin "1") (pinfunction "1_1") (pintype "passive"))
      (node (ref "C38") (pin "1") (pinfunction "1_1") (pintype "passive"))
      (node (ref "C39") (pin "1") (pinfunction "1_1") (pintype "passive"))
      (node (ref "C5") (pin "1") (pinfunction "1_1") (pintype "passive"))
      (node (ref "DS1") (pin "7") (pinfunction "VDD_7") (pintype "bidirectional"))
      (node (ref "DS1") (pin "MH1") (pinfunction "MH1_MH1") (pintype "bidirectional"))
      (node (ref "IC1") (pin "100") (pinfunction "VDD_100") (pintype "power_in"))
      (node (ref "IC1") (pin "11") (pinfunction "VDD_11") (pintype "power_in"))
      (node (ref "IC1") (pin "19") (pinfunction "VDD_19") (pintype "power_in"))
      (node (ref "IC1") (pin "21") (pinfunction "VREF+_21") (pintype "power_in"))
      (node (ref "IC1") (pin "22") (pinfunction "VDDA_22") (pintype "power_in"))
      (node (ref "IC1") (pin "28") (pinfunction "VDD_28") (pintype "power_in"))
      (node (ref "IC1") (pin "50") (pinfunction "VDD_50") (pintype "power_in"))
      (node (ref "IC1") (pin "6") (pinfunction "VBAT_6") (pintype "power_in"))
      (node (ref "IC1") (pin "75") (pinfunction "VDD_75") (pintype "power_in"))
      (node (ref "IC2") (pin "12") (pinfunction "3.3V_12") (pintype "bidirectional"))
      (node (ref "JP22") (pin "1") (pinfunction "1_1") (pintype "passive"))
      (node (ref "R25") (pin "2") (pinfunction "2_2") (pintype "passive"))
      (node (ref "R36") (pin "1") (pinfunction "1_1") (pintype "passive"))
      (node (ref "R37") (pin "2") (pinfunction "2_2") (pintype "passive"))
      (node (ref "S1") (pin "3") (pinfunction "3_3") (pintype "passive"))
      (node (ref "S2") (pin "3") (pinfunction "3_3") (pintype "passive"))
      (node (ref "S3") (pin "2") (pinfunction "2_2") (pintype "passive"))
      (node (ref "S3") (pin "4") (pinfunction "4_4") (pintype "passive"))
      (node (ref "U2") (pin "2") (pinfunction "VOUT_2") (pintype "passive"))
      (node (ref "U2") (pin "3") (pinfunction "SENSE_3") (pintype "passive"))
    )
    (net (code "95") (name "VREF_EXT") (class "Default")
      (node (ref "JP51") (pin "1") (pinfunction "1_1") (pintype "passive"))
      (node (ref "R25") (pin "1") (pinfunction "1_1") (pintype "passive"))
    )
    (net (code "96") (name "unconnected-(IC1-PA1-Pad24)") (class "Default")
      (node (ref "IC1") (pin "24") (pinfunction "PA1_24") (pintype "bidirectional"))
    )
    (net (code "97") (name "unconnected-(IC1-PA8-Pad67)") (class "Default")
      (node (ref "IC1") (pin "67") (pinfunction "PA8_67") (pintype "bidirectional"))
    )
    (net (code "98") (name "unconnected-(IC1-PA9-Pad68)") (class "Default")
      (node (ref "IC1") (pin "68") (pinfunction "PA9_68") (pintype "bidirectional"))
    )
    (net (code "99") (name "unconnected-(IC1-PA10-Pad69)") (class "Default")
      (node (ref "IC1") (pin "69") (pinfunction "PA10_69") (pintype "bidirectional"))
    )
    (net (code "100") (name "unconnected-(IC1-PA11-Pad70)") (class "Default")
      (node (ref "IC1") (pin "70") (pinfunction "PA11_70") (pintype "bidirectional"))
    )
    (net (code "101") (name "unconnected-(IC1-PA12-Pad71)") (class "Default")
      (node (ref "IC1") (pin "71") (pinfunction "PA12_71") (pintype "bidirectional"))
    )
    (net (code "102") (name "unconnected-(IC1-PB2-Pad37)") (class "Default")
      (node (ref "IC1") (pin "37") (pinfunction "PB2_37") (pintype "bidirectional"))
    )
    (net (code "103") (name "unconnected-(IC1-PB10-Pad47)") (class "Default")
      (node (ref "IC1") (pin "47") (pinfunction "PB10_47") (pintype "bidirectional"))
    )
    (net (code "104") (name "unconnected-(IC1-PB11-Pad48)") (class "Default")
      (node (ref "IC1") (pin "48") (pinfunction "PB11_48") (pintype "bidirectional"))
    )
    (net (code "105") (name "unconnected-(IC1-PC0-Pad15)") (class "Default")
      (node (ref "IC1") (pin "15") (pinfunction "PC0_15") (pintype "bidirectional"))
    )
    (net (code "106") (name "unconnected-(IC1-PC1-Pad16)") (class "Default")
      (node (ref "IC1") (pin "16") (pinfunction "PC1_16") (pintype "bidirectional"))
    )
    (net (code "107") (name "unconnected-(IC1-PC2-Pad17)") (class "Default")
      (node (ref "IC1") (pin "17") (pinfunction "PC2_17") (pintype "bidirectional"))
    )
    (net (code "108") (name "unconnected-(IC1-PC3-Pad18)") (class "Default")
      (node (ref "IC1") (pin "18") (pinfunction "PC3_18") (pintype "bidirectional"))
    )
    (net (code "109") (name "unconnected-(IC1-PC6-Pad63)") (class "Default")
      (node (ref "IC1") (pin "63") (pinfunction "PC6_63") (pintype "bidirectional"))
    )
    (net (code "110") (name "unconnected-(IC1-PC7-Pad64)") (class "Default")
      (node (ref "IC1") (pin "64") (pinfunction "PC7_64") (pintype "bidirectional"))
    )
    (net (code "111") (name "unconnected-(IC1-PC8-Pad65)") (class "Default")
      (node (ref "IC1") (pin "65") (pinfunction "PC8_65") (pintype "bidirectional"))
    )
    (net (code "112") (name "unconnected-(IC1-PC9-Pad66)") (class "Default")
      (node (ref "IC1") (pin "66") (pinfunction "PC9_66") (pintype "bidirectional"))
    )
    (net (code "113") (name "unconnected-(IC1-PC11-Pad79)") (class "Default")
      (node (ref "IC1") (pin "79") (pinfunction "PC11_79") (pintype "bidirectional"))
    )
    (net (code "114") (name "unconnected-(IC1-PC13-Pad7)") (class "Default")
      (node (ref "IC1") (pin "7") (pinfunction "PC13_7") (pintype "bidirectional"))
    )
    (net (code "115") (name "unconnected-(IC1-PC14-Pad8)") (class "Default")
      (node (ref "IC1") (pin "8") (pinfunction "PC14_8") (pintype "bidirectional"))
    )
    (net (code "116") (name "unconnected-(IC1-PC15-Pad9)") (class "Default")
      (node (ref "IC1") (pin "9") (pinfunction "PC15_9") (pintype "bidirectional"))
    )
    (net (code "117") (name "unconnected-(IC1-PD0-Pad81)") (class "Default")
      (node (ref "IC1") (pin "81") (pinfunction "PD0_81") (pintype "bidirectional"))
    )
    (net (code "118") (name "unconnected-(IC1-PD1-Pad82)") (class "Default")
      (node (ref "IC1") (pin "82") (pinfunction "PD1_82") (pintype "bidirectional"))
    )
    (net (code "119") (name "unconnected-(IC1-PD3-Pad84)") (class "Default")
      (node (ref "IC1") (pin "84") (pinfunction "PD3_84") (pintype "bidirectional"))
    )
    (net (code "120") (name "unconnected-(IC1-PD4-Pad85)") (class "Default")
      (node (ref "IC1") (pin "85") (pinfunction "PD4_85") (pintype "bidirectional"))
    )
    (net (code "121") (name "unconnected-(IC1-PD5-Pad86)") (class "Default")
      (node (ref "IC1") (pin "86") (pinfunction "PD5_86") (pintype "bidirectional"))
    )
    (net (code "122") (name "unconnected-(IC1-PD6-Pad87)") (class "Default")
      (node (ref "IC1") (pin "87") (pinfunction "PD6_87") (pintype "bidirectional"))
    )
    (net (code "123") (name "unconnected-(IC1-PD7-Pad88)") (class "Default")
      (node (ref "IC1") (pin "88") (pinfunction "PD7_88") (pintype "bidirectional"))
    )
    (net (code "124") (name "unconnected-(IC1-PE1-Pad98)") (class "Default")
      (node (ref "IC1") (pin "98") (pinfunction "PE1_98") (pintype "bidirectional"))
    )
    (net (code "125") (name "unconnected-(IC1-PE3-Pad2)") (class "Default")
      (node (ref "IC1") (pin "2") (pinfunction "PE3_2") (pintype "bidirectional"))
    )
    (net (code "126") (name "unconnected-(IC1-PE5-Pad4)") (class "Default")
      (node (ref "IC1") (pin "4") (pinfunction "PE5_4") (pintype "bidirectional"))
    )
    (net (code "127") (name "unconnected-(IC1-PE7-Pad38)") (class "Default")
      (node (ref "IC1") (pin "38") (pinfunction "PE7_38") (pintype "bidirectional"))
    )
    (net (code "128") (name "unconnected-(IC1-PE13-Pad44)") (class "Default")
      (node (ref "IC1") (pin "44") (pinfunction "PE13_44") (pintype "bidirectional"))
    )
    (net (code "129") (name "unconnected-(IC1-PE14-Pad45)") (class "Default")
      (node (ref "IC1") (pin "45") (pinfunction "PE14_45") (pintype "bidirectional"))
    )
    (net (code "130") (name "unconnected-(IC1-PE15-Pad46)") (class "Default")
      (node (ref "IC1") (pin "46") (pinfunction "PE15_46") (pintype "bidirectional"))
    )
    (net (code "131") (name "unconnected-(IC2-AIO0-Pad9)") (class "Default")
      (node (ref "IC2") (pin "9") (pinfunction "AIO0_9") (pintype "bidirectional"))
    )
    (net (code "132") (name "unconnected-(IC2-AIO1-Pad10)") (class "Default")
      (node (ref "IC2") (pin "10") (pinfunction "AIO1_10") (pintype "bidirectional"))
    )
    (net (code "133") (name "unconnected-(IC2-CLK-Pad19)") (class "Default")
      (node (ref "IC2") (pin "19") (pinfunction "CLK_19") (pintype "bidirectional"))
    )
    (net (code "134") (name "unconnected-(IC2-CSB-Pad16)") (class "Default")
      (node (ref "IC2") (pin "16") (pinfunction "CSB_16") (pintype "bidirectional"))
    )
    (net (code "135") (name "unconnected-(IC2-CTS-Pad3)") (class "Default")
      (node (ref "IC2") (pin "3") (pinfunction "CTS_3") (pintype "bidirectional"))
    )
    (net (code "136") (name "unconnected-(IC2-MISO-Pad18)") (class "Default")
      (node (ref "IC2") (pin "18") (pinfunction "MISO_18") (pintype "bidirectional"))
    )
    (net (code "137") (name "unconnected-(IC2-MOSI-Pad17)") (class "Default")
      (node (ref "IC2") (pin "17") (pinfunction "MOSI_17") (pintype "bidirectional"))
    )
    (net (code "138") (name "unconnected-(IC2-NC-Pad14)") (class "Default")
      (node (ref "IC2") (pin "14") (pinfunction "NC_14") (pintype "no_connect"))
    )
    (net (code "139") (name "unconnected-(IC2-PCK_CLK-Pad5)") (class "Default")
      (node (ref "IC2") (pin "5") (pinfunction "PCK_CLK_5") (pintype "bidirectional"))
    )
    (net (code "140") (name "unconnected-(IC2-PCM_IN-Pad7)") (class "Default")
      (node (ref "IC2") (pin "7") (pinfunction "PCM_IN_7") (pintype "bidirectional"))
    )
    (net (code "141") (name "unconnected-(IC2-PCM_OUT-Pad6)") (class "Default")
      (node (ref "IC2") (pin "6") (pinfunction "PCM_OUT_6") (pintype "bidirectional"))
    )
    (net (code "142") (name "unconnected-(IC2-PIO0-Pad23)") (class "Default")
      (node (ref "IC2") (pin "23") (pinfunction "PIO0_23") (pintype "bidirectional"))
    )
    (net (code "143") (name "unconnected-(IC2-PIO2-Pad25)") (class "Default")
      (node (ref "IC2") (pin "25") (pinfunction "PIO2_25") (pintype "bidirectional"))
    )
    (net (code "144") (name "unconnected-(IC2-PIO4-Pad27)") (class "Default")
      (node (ref "IC2") (pin "27") (pinfunction "PIO4_27") (pintype "bidirectional"))
    )
    (net (code "145") (name "unconnected-(IC2-PIO5-Pad28)") (class "Default")
      (node (ref "IC2") (pin "28") (pinfunction "PIO5_28") (pintype "bidirectional"))
    )
    (net (code "146") (name "unconnected-(IC2-PIO6-Pad29)") (class "Default")
      (node (ref "IC2") (pin "29") (pinfunction "PIO6_29") (pintype "bidirectional"))
    )
    (net (code "147") (name "unconnected-(IC2-PIO7-Pad30)") (class "Default")
      (node (ref "IC2") (pin "30") (pinfunction "PIO7_30") (pintype "bidirectional"))
    )
    (net (code "148") (name "unconnected-(IC2-PIO8-Pad31)") (class "Default")
      (node (ref "IC2") (pin "31") (pinfunction "PIO8_31") (pintype "bidirectional"))
    )
    (net (code "149") (name "unconnected-(IC2-PIO9-Pad32)") (class "Default")
      (node (ref "IC2") (pin "32") (pinfunction "PIO9_32") (pintype "bidirectional"))
    )
    (net (code "150") (name "unconnected-(IC2-PIO10-Pad33)") (class "Default")
      (node (ref "IC2") (pin "33") (pinfunction "PIO10_33") (pintype "bidirectional"))
    )
    (net (code "151") (name "unconnected-(IC2-PIO11-Pad34)") (class "Default")
      (node (ref "IC2") (pin "34") (pinfunction "PIO11_34") (pintype "bidirectional"))
    )
    (net (code "152") (name "unconnected-(IC2-PSM_SYNC-Pad8)") (class "Default")
      (node (ref "IC2") (pin "8") (pinfunction "PSM_SYNC_8") (pintype "bidirectional"))
    )
    (net (code "153") (name "unconnected-(IC2-RESET-Pad11)") (class "Default")
      (node (ref "IC2") (pin "11") (pinfunction "RESET_11") (pintype "bidirectional"))
    )
    (net (code "154") (name "unconnected-(IC2-RTS-Pad4)") (class "Default")
      (node (ref "IC2") (pin "4") (pinfunction "RTS_4") (pintype "bidirectional"))
    )
    (net (code "155") (name "unconnected-(IC2-USB_D+-Pad20)") (class "Default")
      (node (ref "IC2") (pin "20") (pinfunction "USB_D+_20") (pintype "bidirectional"))
    )
    (net (code "156") (name "unconnected-(IC2-USB_D--Pad15)") (class "Default")
      (node (ref "IC2") (pin "15") (pinfunction "USB_D-_15") (pintype "bidirectional"))
    )
    (net (code "157") (name "unconnected-(U$7-P2-Pad2)") (class "Default")
      (node (ref "U$7") (pin "2") (pinfunction "P2_2") (pintype "bidirectional"))
    )
    (net (code "158") (name "unconnected-(U$9-P2-Pad2)") (class "Default")
      (node (ref "U$9") (pin "2") (pinfunction "P2_2") (pintype "bidirectional"))
    )
    (net (code "159") (name "unconnected-(U$10-P2-Pad2)") (class "Default")
      (node (ref "U$10") (pin "2") (pinfunction "P2_2") (pintype "bidirectional"))
    )
    (net (code "160") (name "unconnected-(U2-VIN_2-Pad7)") (class "Default")
      (node (ref "U2") (pin "7") (pinfunction "VIN_2_7") (pintype "passive"))
    )
    (net (code "161") (name "unconnected-(U2-VOUT_2-Pad1)") (class "Default")
      (node (ref "U2") (pin "1") (pinfunction "VOUT_2_1") (pintype "passive"))
    )
  )
)
